# HiLoRelay.net
KiCad netlist of a schematic drawn in EAGLE
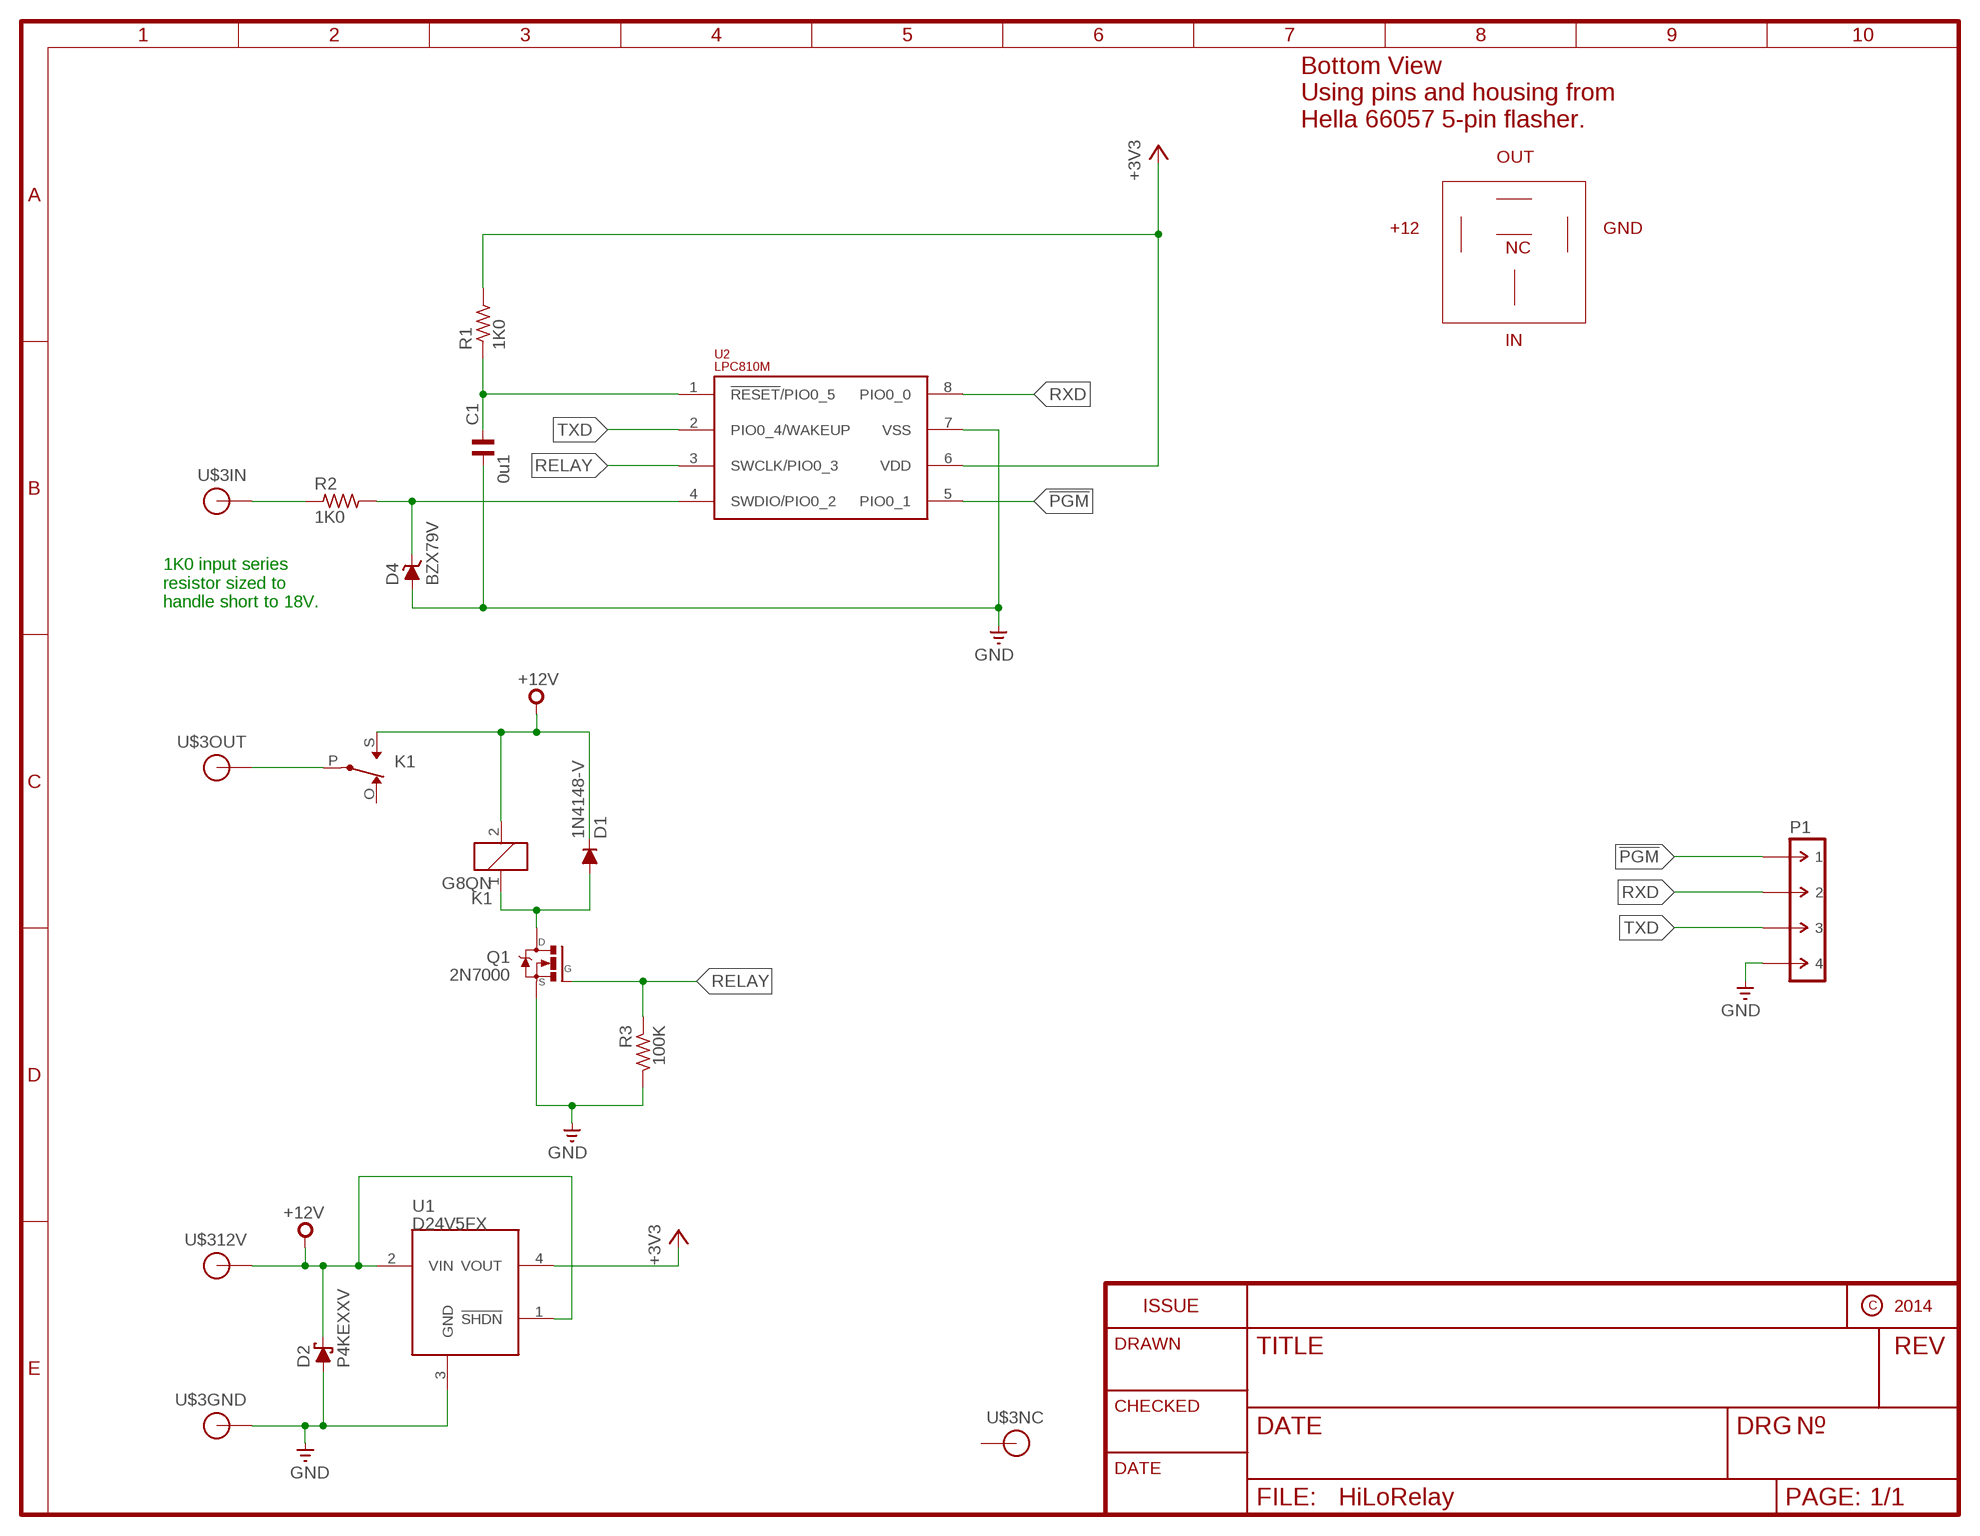
[diagram p0: schematic, sheet 1]

(export (version "E")
  (design (tool "Eeschema 10.0.6"))
  (components
    (comp (ref "C1")
      (value "0u1")
      (footprint "eagle-import:C025-024X044")
      (fields (field (name "PARTNO") "FK18X7R1E104K"))
      (libsource (lib "eagle-import") (part "C-EU025-024X044"))
    )
    (comp (ref "D1")
      (value "1N4148-V")
      (footprint "eagle-import:DO35-V")
      (fields (field (name "PARTNO") "1N4148"))
      (libsource (lib "eagle-import") (part "1N4148-V"))
    )
    (comp (ref "D2")
      (value "P4KEXXV")
      (footprint "eagle-import:DO41-V")
      (fields (field (name "PARTNO") "P4KE30CA"))
      (libsource (lib "eagle-import") (part "P4KEXXV"))
    )
    (comp (ref "D4")
      (value "BZX79V")
      (footprint "eagle-import:DO35-V")
      (fields (field (name "PARTNO") "TZX3V3A-TR"))
      (libsource (lib "eagle-import") (part "BZX79V"))
    )
    (comp (ref "K1")
      (value "G8QN")
      (footprint "eagle-import:G8QN")
      (fields (field (name "PARTNO") "G8QN-1C4-DC12"))
      (libsource (lib "eagle-import") (part "G8QN"))
    )
    (comp (ref "P1")
      (value "M-1X04-SIP-100-32")
      (footprint "eagle-import:SIP-100-04-32")
      (fields (field (name "PARTNO") "961104-6404-AR"))
      (libsource (lib "eagle-import") (part "M-1X04-SIP-100-32"))
    )
    (comp (ref "Q1")
      (value "2N7000")
      (footprint "eagle-import:TO-92")
      (libsource (lib "eagle-import") (part "2N7000"))
    )
    (comp (ref "R1")
      (value "1K0")
      (footprint "eagle-import:0207_2V")
      (fields (field (name "PARTNO") "MFR-25FBF52-1K"))
      (libsource (lib "eagle-import") (part "R-EU_0207/2V"))
    )
    (comp (ref "R2")
      (value "1K0")
      (footprint "eagle-import:0207_2V")
      (fields (field (name "PARTNO") "MFR-25FBF52-1K"))
      (libsource (lib "eagle-import") (part "R-EU_0207/2V"))
    )
    (comp (ref "R3")
      (value "100K")
      (footprint "eagle-import:0207_2V")
      (fields (field (name "PARTNO") "MFR-25FRF52-100K"))
      (libsource (lib "eagle-import") (part "R-EU_0207/2V"))
    )
    (comp (ref "U$3")
      (value "TRIDON_PIN_BASE")
      (footprint "eagle-import:TRIDON_PIN_BASE")
      (fields (field (name "BOM") "EXCLUDE"))
      (libsource (lib "eagle-import") (part "TRIDON_PIN_BASE"))
    )
    (comp (ref "U1")
      (value "D24V5FX")
      (footprint "eagle-import:SIP-100-04-32")
      (libsource (lib "eagle-import") (part "D24V5FX"))
    )
    (comp (ref "U2")
      (value "LPC810M")
      (footprint "eagle-import:DIL08")
      (fields (field (name "PARTNO") "LPC810M021FN8FP"))
      (libsource (lib "eagle-import") (part "LPC810M"))
    )
  )
  (nets
    (net (code "1") (name "+3V3") (class "Default")
      (node (ref "R1") (pin "2") (pinfunction "2_2") (pintype "passive"))
      (node (ref "U1") (pin "4") (pinfunction "VOUT_4") (pintype "bidirectional"))
      (node (ref "U2") (pin "6") (pinfunction "VDD_6") (pintype "bidirectional"))
    )
    (net (code "2") (name "+12V") (class "Default")
      (node (ref "D1") (pin "C") (pinfunction "C_C") (pintype "passive"))
      (node (ref "D2") (pin "C") (pinfunction "C_C") (pintype "passive"))
      (node (ref "K1") (pin "2") (pinfunction "2_2") (pintype "passive"))
      (node (ref "K1") (pin "S") (pinfunction "NO_S") (pintype "passive"))
      (node (ref "U$3") (pin "12V") (pinfunction "P$1_12V") (pintype "bidirectional"))
      (node (ref "U1") (pin "1") (pinfunction "~{SHDN}_1") (pintype "bidirectional"))
      (node (ref "U1") (pin "2") (pinfunction "VIN_2") (pintype "bidirectional"))
    )
    (net (code "3") (name "/~{PGM}") (class "Default")
      (node (ref "P1") (pin "1") (pinfunction "1_1") (pintype "passive"))
      (node (ref "U2") (pin "5") (pinfunction "PIO0_1_5") (pintype "bidirectional"))
    )
    (net (code "4") (name "GND") (class "Default")
      (node (ref "C1") (pin "2") (pinfunction "2_2") (pintype "passive"))
      (node (ref "D2") (pin "A") (pinfunction "A_A") (pintype "passive"))
      (node (ref "D4") (pin "A") (pinfunction "A_A") (pintype "passive"))
      (node (ref "P1") (pin "4") (pinfunction "4_4") (pintype "passive"))
      (node (ref "Q1") (pin "1") (pinfunction "S_1") (pintype "passive"))
      (node (ref "R3") (pin "2") (pinfunction "2_2") (pintype "passive"))
      (node (ref "U$3") (pin "GND") (pinfunction "P$1_GND") (pintype "bidirectional"))
      (node (ref "U1") (pin "3") (pinfunction "GND_3") (pintype "bidirectional"))
      (node (ref "U2") (pin "7") (pinfunction "VSS_7") (pintype "bidirectional"))
    )
    (net (code "5") (name "Net-(K1B-COM)") (class "Default")
      (node (ref "K1") (pin "P") (pinfunction "COM_P") (pintype "passive"))
      (node (ref "U$3") (pin "OUT") (pinfunction "P$1_OUT") (pintype "bidirectional"))
    )
    (net (code "6") (name "Net-(Q1-D)") (class "Default")
      (node (ref "D1") (pin "A") (pinfunction "A_A") (pintype "passive"))
      (node (ref "K1") (pin "1") (pinfunction "1_1") (pintype "passive"))
      (node (ref "Q1") (pin "3") (pinfunction "D_3") (pintype "passive"))
    )
    (net (code "7") (name "Net-(U$3C-P$1)") (class "Default")
      (node (ref "R2") (pin "1") (pinfunction "1_1") (pintype "passive"))
      (node (ref "U$3") (pin "IN") (pinfunction "P$1_IN") (pintype "bidirectional"))
    )
    (net (code "8") (name "Net-(U2-SWDIO{slash}PIO0_2)") (class "Default")
      (node (ref "D4") (pin "C") (pinfunction "C_C") (pintype "passive"))
      (node (ref "R2") (pin "2") (pinfunction "2_2") (pintype "passive"))
      (node (ref "U2") (pin "4") (pinfunction "SWDIO/PIO0_2_4") (pintype "bidirectional"))
    )
    (net (code "9") (name "Net-(U2-~{RESET}{slash}PIO0_5)") (class "Default")
      (node (ref "C1") (pin "1") (pinfunction "1_1") (pintype "passive"))
      (node (ref "R1") (pin "1") (pinfunction "1_1") (pintype "passive"))
      (node (ref "U2") (pin "1") (pinfunction "~{RESET}/PIO0_5_1") (pintype "bidirectional"))
    )
    (net (code "10") (name "RELAY") (class "Default")
      (node (ref "Q1") (pin "2") (pinfunction "G_2") (pintype "passive"))
      (node (ref "R3") (pin "1") (pinfunction "1_1") (pintype "passive"))
      (node (ref "U2") (pin "3") (pinfunction "SWCLK/PIO0_3_3") (pintype "bidirectional"))
    )
    (net (code "11") (name "RXD") (class "Default")
      (node (ref "P1") (pin "2") (pinfunction "2_2") (pintype "passive"))
      (node (ref "U2") (pin "8") (pinfunction "PIO0_0_8") (pintype "bidirectional"))
    )
    (net (code "12") (name "TXD") (class "Default")
      (node (ref "P1") (pin "3") (pinfunction "3_3") (pintype "passive"))
      (node (ref "U2") (pin "2") (pinfunction "PIO0_4/WAKEUP_2") (pintype "bidirectional"))
    )
    (net (code "13") (name "unconnected-(K1B-NC-PadO)") (class "Default")
      (node (ref "K1") (pin "O") (pinfunction "NC_O") (pintype "passive"))
    )
    (net (code "14") (name "unconnected-(U$3D-P$1-PadNC)") (class "Default")
      (node (ref "U$3") (pin "NC") (pinfunction "P$1_NC") (pintype "bidirectional"))
    )
  )
)
